# Humus_ethernet_dip_v4.net
KiCad netlist of a schematic drawn in EAGLE
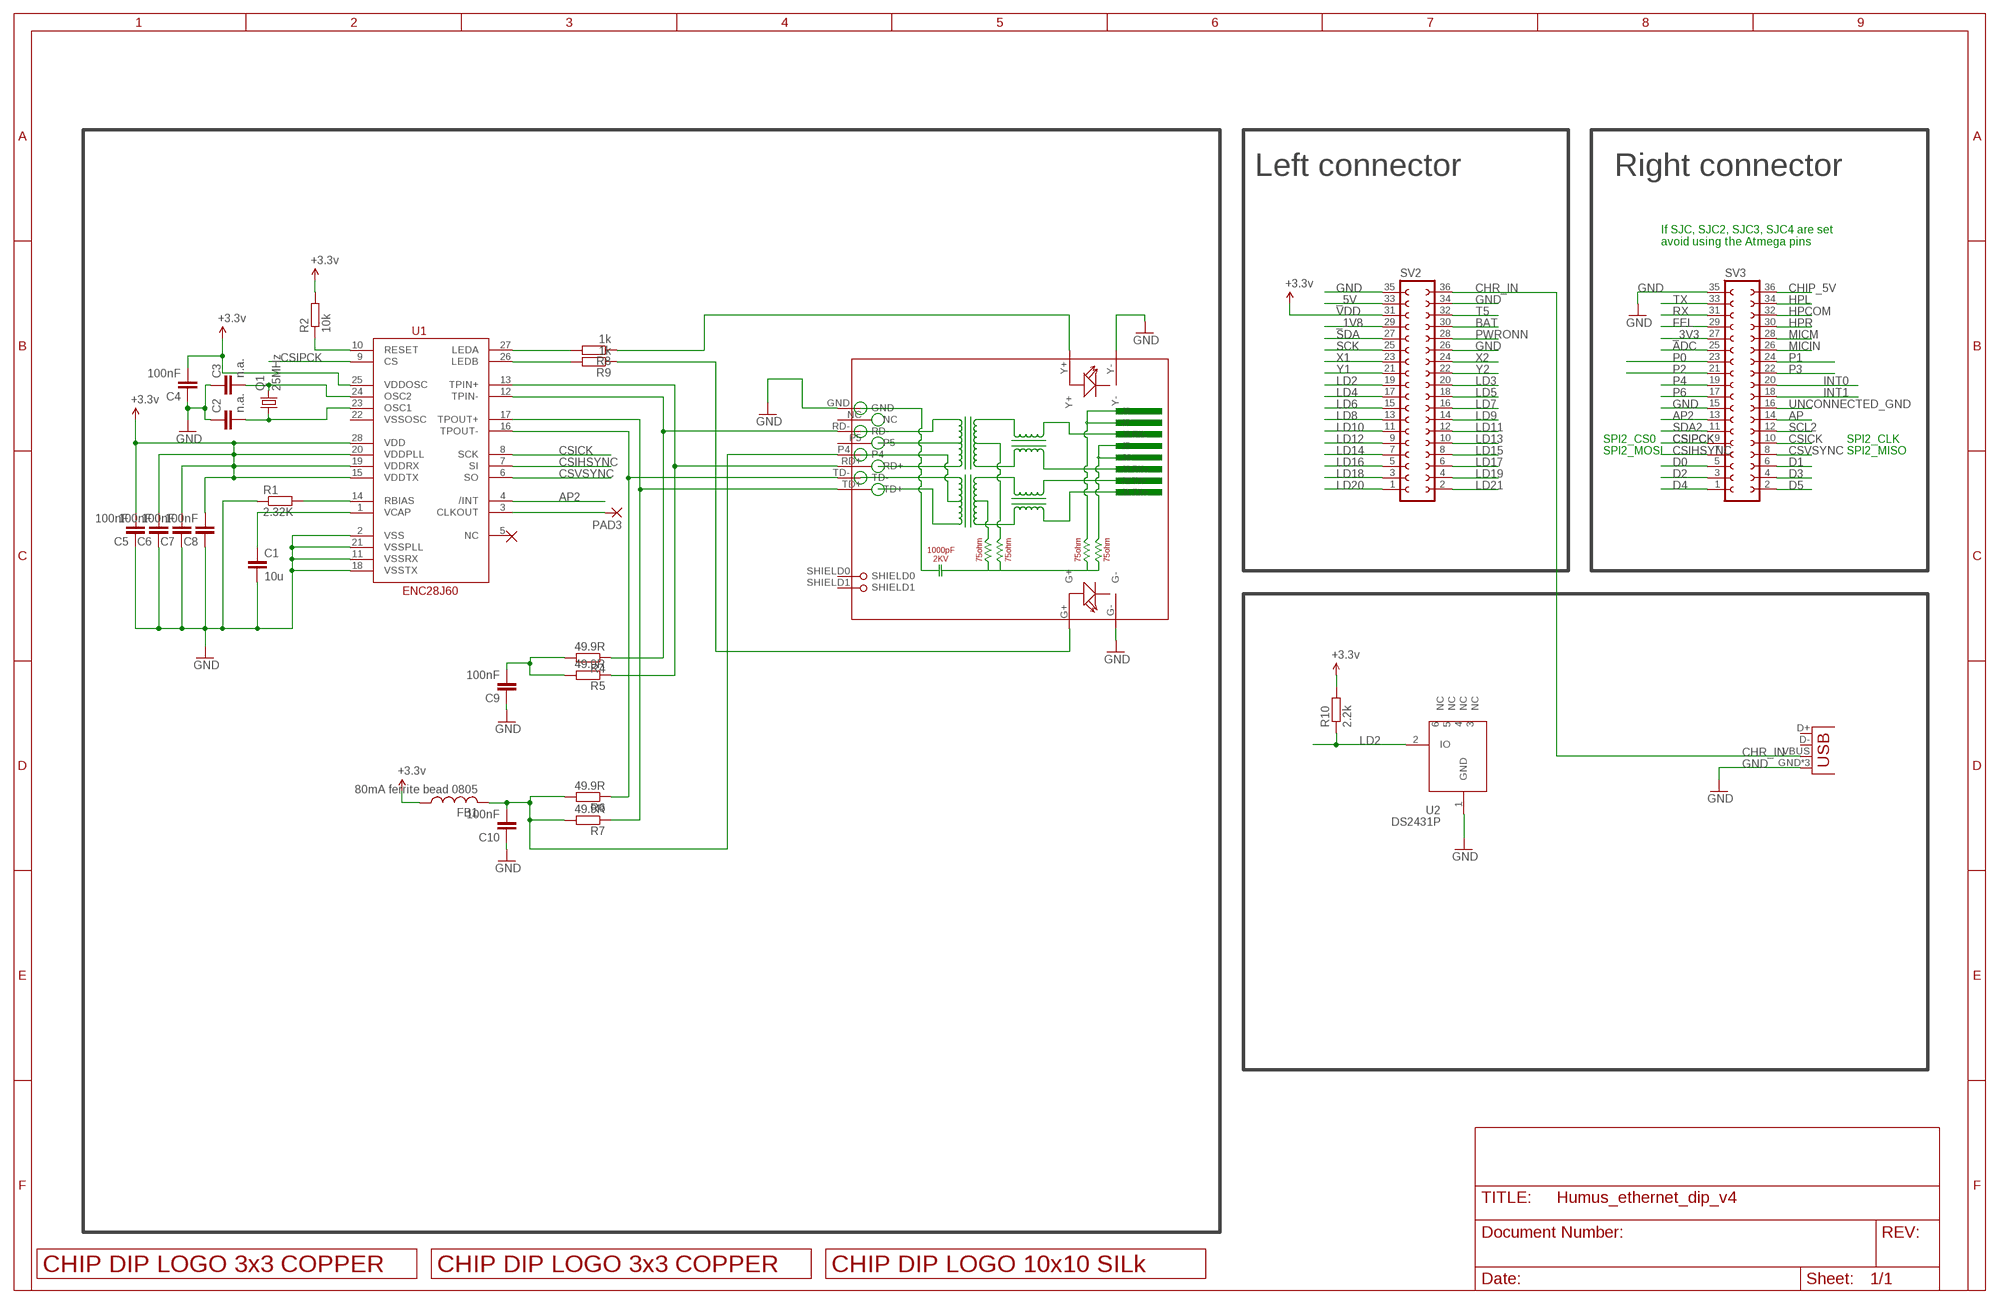
[diagram p0: schematic, sheet 1]

(export (version "E")
  (design (tool "Eeschema 10.0.6"))
  (components
    (comp (ref "C1")
      (value "10u")
      (footprint "eagle-import:C0805")
      (libsource (lib "eagle-import") (part "C-EUC0805"))
    )
    (comp (ref "C2")
      (value "n.a.")
      (footprint "eagle-import:C0805")
      (libsource (lib "eagle-import") (part "C-EUC0805"))
    )
    (comp (ref "C3")
      (value "n.a.")
      (footprint "eagle-import:C0805")
      (libsource (lib "eagle-import") (part "C-EUC0805"))
    )
    (comp (ref "C4")
      (value "100nF")
      (footprint "eagle-import:C0805")
      (libsource (lib "eagle-import") (part "C-EUC0805"))
    )
    (comp (ref "C5")
      (value "100nF")
      (footprint "eagle-import:C0805")
      (libsource (lib "eagle-import") (part "C-EUC0805"))
    )
    (comp (ref "C6")
      (value "100nF")
      (footprint "eagle-import:C0805")
      (libsource (lib "eagle-import") (part "C-EUC0805"))
    )
    (comp (ref "C7")
      (value "100nF")
      (footprint "eagle-import:C0805")
      (libsource (lib "eagle-import") (part "C-EUC0805"))
    )
    (comp (ref "C8")
      (value "100nF")
      (footprint "eagle-import:C0805")
      (libsource (lib "eagle-import") (part "C-EUC0805"))
    )
    (comp (ref "C9")
      (value "100nF")
      (footprint "eagle-import:C0805")
      (libsource (lib "eagle-import") (part "C-EUC0805"))
    )
    (comp (ref "C10")
      (value "100nF")
      (footprint "eagle-import:C0805")
      (libsource (lib "eagle-import") (part "C-EUC0805"))
    )
    (comp (ref "FB1")
      (value "80mA ferrite bead 0805")
      (footprint "eagle-import:0805")
      (libsource (lib "eagle-import") (part "FERRITE-BEADB"))
    )
    (comp (ref "PAD3")
      (value "WIREPADSMD1,27-254")
      (footprint "eagle-import:SMD1,27-2,54")
      (libsource (lib "eagle-import") (part "WIREPADSMD1,27-254"))
    )
    (comp (ref "Q1")
      (value "25MHz")
      (footprint "eagle-import:SM49")
      (libsource (lib "eagle-import") (part "CRYSTALSM49"))
    )
    (comp (ref "R1")
      (value "2.32K")
      (footprint "eagle-import:R0805")
      (libsource (lib "eagle-import") (part "R-EU_R0805"))
    )
    (comp (ref "R2")
      (value "10k")
      (footprint "eagle-import:R0805")
      (libsource (lib "eagle-import") (part "R-EU_R0805"))
    )
    (comp (ref "R4")
      (value "49.9R")
      (footprint "eagle-import:R0805")
      (libsource (lib "eagle-import") (part "R-EU_R0805"))
    )
    (comp (ref "R5")
      (value "49.9R")
      (footprint "eagle-import:R0805")
      (libsource (lib "eagle-import") (part "R-EU_R0805"))
    )
    (comp (ref "R6")
      (value "49.9R")
      (footprint "eagle-import:R0805")
      (libsource (lib "eagle-import") (part "R-EU_R0805"))
    )
    (comp (ref "R7")
      (value "49.9R")
      (footprint "eagle-import:R0805")
      (libsource (lib "eagle-import") (part "R-EU_R0805"))
    )
    (comp (ref "R8")
      (value "1k")
      (footprint "eagle-import:R0805")
      (libsource (lib "eagle-import") (part "R-EU_R0805"))
    )
    (comp (ref "R9")
      (value "1k")
      (footprint "eagle-import:R0805")
      (libsource (lib "eagle-import") (part "R-EU_R0805"))
    )
    (comp (ref "R10")
      (value "2.2k")
      (footprint "eagle-import:R0805")
      (libsource (lib "eagle-import") (part "R-EU_R0805"))
    )
    (comp (ref "RJ1")
      (value "HR911105A")
      (footprint "eagle-import:HR911105A")
      (libsource (lib "eagle-import") (part "HR911105A"))
    )
    (comp (ref "SV2")
      (value "FE18-2")
      (footprint "eagle-import:FE18-2")
      (libsource (lib "eagle-import") (part "FE18-2"))
    )
    (comp (ref "SV3")
      (value "FE18-2")
      (footprint "eagle-import:FE18-2")
      (libsource (lib "eagle-import") (part "FE18-2"))
    )
    (comp (ref "U$1")
      (value "LOGO_10X10_SILK")
      (footprint "eagle-import:LOGO2_10X10_SILK")
      (libsource (lib "eagle-import") (part "LOGO_10X10_SILK"))
    )
    (comp (ref "U$2")
      (value "LOGO_3X3_COPPER")
      (footprint "eagle-import:LOGO_3X3_COPPER")
      (libsource (lib "eagle-import") (part "LOGO_3X3_COPPER"))
    )
    (comp (ref "U$4")
      (value "LOGO_3X3_COPPER")
      (footprint "eagle-import:LOGO_3X3_COPPER")
      (libsource (lib "eagle-import") (part "LOGO_3X3_COPPER"))
    )
    (comp (ref "U1")
      (value "ENC28J60SS")
      (footprint "eagle-import:SSOP28DB")
      (libsource (lib "eagle-import") (part "ENC28J60"))
    )
    (comp (ref "U2")
      (value "DS2431P")
      (footprint "eagle-import:TSOC6")
      (fields (field (name "MFG") "DIGIKEY") (field (name "VENDOR_PART_NUMBER") "DS2431P+T&R"))
      (libsource (lib "eagle-import") (part "DS2431P"))
    )
    (comp (ref "USB")
      (value "USBUSB-MICROB-SMT-DIP")
      (footprint "eagle-import:USB-MICROB-SMT-DIP")
      (libsource (lib "eagle-import") (part "USBUSB-MICROB-SMT-DIP"))
    )
  )
  (nets
    (net (code "1") (name "+3.3v") (class "Default")
      (node (ref "C4") (pin "2") (pinfunction "2_2") (pintype "passive"))
      (node (ref "C5") (pin "2") (pinfunction "2_2") (pintype "passive"))
      (node (ref "C6") (pin "2") (pinfunction "2_2") (pintype "passive"))
      (node (ref "C7") (pin "2") (pinfunction "2_2") (pintype "passive"))
      (node (ref "C8") (pin "2") (pinfunction "2_2") (pintype "passive"))
      (node (ref "FB1") (pin "1") (pinfunction "1_1") (pintype "passive"))
      (node (ref "R10") (pin "2") (pinfunction "2_2") (pintype "passive"))
      (node (ref "R2") (pin "2") (pinfunction "2_2") (pintype "passive"))
      (node (ref "SV2") (pin "31") (pinfunction "31_31") (pintype "passive"))
      (node (ref "U1") (pin "15") (pinfunction "VDDTX_15") (pintype "bidirectional"))
      (node (ref "U1") (pin "19") (pinfunction "VDDRX_19") (pintype "bidirectional"))
      (node (ref "U1") (pin "20") (pinfunction "VDDPLL_20") (pintype "bidirectional"))
      (node (ref "U1") (pin "25") (pinfunction "VDDOSC_25") (pintype "bidirectional"))
      (node (ref "U1") (pin "28") (pinfunction "VDD_28") (pintype "bidirectional"))
    )
    (net (code "2") (name "/ADC") (class "Default")
      (node (ref "SV3") (pin "25") (pinfunction "25_25") (pintype "passive"))
    )
    (net (code "3") (name "/AP") (class "Default")
      (node (ref "SV3") (pin "14") (pinfunction "14_14") (pintype "passive"))
    )
    (net (code "4") (name "/AP2") (class "Default")
      (node (ref "SV3") (pin "13") (pinfunction "13_13") (pintype "passive"))
      (node (ref "U1") (pin "4") (pinfunction "/INT_4") (pintype "bidirectional"))
    )
    (net (code "5") (name "/BAT") (class "Default")
      (node (ref "SV2") (pin "30") (pinfunction "30_30") (pintype "passive"))
    )
    (net (code "6") (name "/CHIP_5V") (class "Default")
      (node (ref "SV3") (pin "36") (pinfunction "36_36") (pintype "passive"))
    )
    (net (code "7") (name "/CHR_IN") (class "Default")
      (node (ref "SV2") (pin "36") (pinfunction "36_36") (pintype "passive"))
      (node (ref "USB") (pin "VBUS") (pinfunction "VBUS_VBUS") (pintype "bidirectional"))
    )
    (net (code "8") (name "/CSICK") (class "Default")
      (node (ref "SV3") (pin "10") (pinfunction "10_10") (pintype "passive"))
      (node (ref "U1") (pin "8") (pinfunction "SCK_8") (pintype "bidirectional"))
    )
    (net (code "9") (name "/CSIHSYNC") (class "Default")
      (node (ref "SV3") (pin "7") (pinfunction "7_7") (pintype "passive"))
      (node (ref "U1") (pin "7") (pinfunction "SI_7") (pintype "bidirectional"))
    )
    (net (code "10") (name "/CSIPCK") (class "Default")
      (node (ref "SV3") (pin "9") (pinfunction "9_9") (pintype "passive"))
      (node (ref "U1") (pin "9") (pinfunction "CS_9") (pintype "bidirectional"))
    )
    (net (code "11") (name "/CSVSYNC") (class "Default")
      (node (ref "SV3") (pin "8") (pinfunction "8_8") (pintype "passive"))
      (node (ref "U1") (pin "6") (pinfunction "SO_6") (pintype "bidirectional"))
    )
    (net (code "12") (name "/D0") (class "Default")
      (node (ref "SV3") (pin "5") (pinfunction "5_5") (pintype "passive"))
    )
    (net (code "13") (name "/D1") (class "Default")
      (node (ref "SV3") (pin "6") (pinfunction "6_6") (pintype "passive"))
    )
    (net (code "14") (name "/D2") (class "Default")
      (node (ref "SV3") (pin "3") (pinfunction "3_3") (pintype "passive"))
    )
    (net (code "15") (name "/D3") (class "Default")
      (node (ref "SV3") (pin "4") (pinfunction "4_4") (pintype "passive"))
    )
    (net (code "16") (name "/D4") (class "Default")
      (node (ref "SV3") (pin "1") (pinfunction "1_1") (pintype "passive"))
    )
    (net (code "17") (name "/D5") (class "Default")
      (node (ref "SV3") (pin "2") (pinfunction "2_2") (pintype "passive"))
    )
    (net (code "18") (name "/FEL") (class "Default")
      (node (ref "SV3") (pin "29") (pinfunction "29_29") (pintype "passive"))
    )
    (net (code "19") (name "/HPCOM") (class "Default")
      (node (ref "SV3") (pin "32") (pinfunction "32_32") (pintype "passive"))
    )
    (net (code "20") (name "/HPL") (class "Default")
      (node (ref "SV3") (pin "34") (pinfunction "34_34") (pintype "passive"))
    )
    (net (code "21") (name "/HPR") (class "Default")
      (node (ref "SV3") (pin "30") (pinfunction "30_30") (pintype "passive"))
    )
    (net (code "22") (name "/INT0") (class "Default")
      (node (ref "SV3") (pin "20") (pinfunction "20_20") (pintype "passive"))
    )
    (net (code "23") (name "/INT1") (class "Default")
      (node (ref "SV3") (pin "18") (pinfunction "18_18") (pintype "passive"))
    )
    (net (code "24") (name "/LD2") (class "Default")
      (node (ref "R10") (pin "1") (pinfunction "1_1") (pintype "passive"))
      (node (ref "SV2") (pin "19") (pinfunction "19_19") (pintype "passive"))
      (node (ref "U2") (pin "2") (pinfunction "IO_2") (pintype "bidirectional"))
    )
    (net (code "25") (name "/LD3") (class "Default")
      (node (ref "SV2") (pin "20") (pinfunction "20_20") (pintype "passive"))
    )
    (net (code "26") (name "/LD4") (class "Default")
      (node (ref "SV2") (pin "17") (pinfunction "17_17") (pintype "passive"))
    )
    (net (code "27") (name "/LD5") (class "Default")
      (node (ref "SV2") (pin "18") (pinfunction "18_18") (pintype "passive"))
    )
    (net (code "28") (name "/LD6") (class "Default")
      (node (ref "SV2") (pin "15") (pinfunction "15_15") (pintype "passive"))
    )
    (net (code "29") (name "/LD7") (class "Default")
      (node (ref "SV2") (pin "16") (pinfunction "16_16") (pintype "passive"))
    )
    (net (code "30") (name "/LD8") (class "Default")
      (node (ref "SV2") (pin "13") (pinfunction "13_13") (pintype "passive"))
    )
    (net (code "31") (name "/LD9") (class "Default")
      (node (ref "SV2") (pin "14") (pinfunction "14_14") (pintype "passive"))
    )
    (net (code "32") (name "/LD10") (class "Default")
      (node (ref "SV2") (pin "11") (pinfunction "11_11") (pintype "passive"))
    )
    (net (code "33") (name "/LD11") (class "Default")
      (node (ref "SV2") (pin "12") (pinfunction "12_12") (pintype "passive"))
    )
    (net (code "34") (name "/LD12") (class "Default")
      (node (ref "SV2") (pin "9") (pinfunction "9_9") (pintype "passive"))
    )
    (net (code "35") (name "/LD13") (class "Default")
      (node (ref "SV2") (pin "10") (pinfunction "10_10") (pintype "passive"))
    )
    (net (code "36") (name "/LD14") (class "Default")
      (node (ref "SV2") (pin "7") (pinfunction "7_7") (pintype "passive"))
    )
    (net (code "37") (name "/LD15") (class "Default")
      (node (ref "SV2") (pin "8") (pinfunction "8_8") (pintype "passive"))
    )
    (net (code "38") (name "/LD16") (class "Default")
      (node (ref "SV2") (pin "5") (pinfunction "5_5") (pintype "passive"))
    )
    (net (code "39") (name "/LD17") (class "Default")
      (node (ref "SV2") (pin "6") (pinfunction "6_6") (pintype "passive"))
    )
    (net (code "40") (name "/LD18") (class "Default")
      (node (ref "SV2") (pin "3") (pinfunction "3_3") (pintype "passive"))
    )
    (net (code "41") (name "/LD19") (class "Default")
      (node (ref "SV2") (pin "4") (pinfunction "4_4") (pintype "passive"))
    )
    (net (code "42") (name "/LD20") (class "Default")
      (node (ref "SV2") (pin "1") (pinfunction "1_1") (pintype "passive"))
    )
    (net (code "43") (name "/LD21") (class "Default")
      (node (ref "SV2") (pin "2") (pinfunction "2_2") (pintype "passive"))
    )
    (net (code "44") (name "/MICIN") (class "Default")
      (node (ref "SV3") (pin "26") (pinfunction "26_26") (pintype "passive"))
    )
    (net (code "45") (name "/MICM") (class "Default")
      (node (ref "SV3") (pin "28") (pinfunction "28_28") (pintype "passive"))
    )
    (net (code "46") (name "/P0") (class "Default")
      (node (ref "SV3") (pin "23") (pinfunction "23_23") (pintype "passive"))
    )
    (net (code "47") (name "/P1") (class "Default")
      (node (ref "SV3") (pin "24") (pinfunction "24_24") (pintype "passive"))
    )
    (net (code "48") (name "/P2") (class "Default")
      (node (ref "SV3") (pin "21") (pinfunction "21_21") (pintype "passive"))
    )
    (net (code "49") (name "/P3") (class "Default")
      (node (ref "SV3") (pin "22") (pinfunction "22_22") (pintype "passive"))
    )
    (net (code "50") (name "/P4") (class "Default")
      (node (ref "SV3") (pin "19") (pinfunction "19_19") (pintype "passive"))
    )
    (net (code "51") (name "/P6") (class "Default")
      (node (ref "SV3") (pin "17") (pinfunction "17_17") (pintype "passive"))
    )
    (net (code "52") (name "/PWRONN") (class "Default")
      (node (ref "SV2") (pin "28") (pinfunction "28_28") (pintype "passive"))
    )
    (net (code "53") (name "/RX") (class "Default")
      (node (ref "SV3") (pin "31") (pinfunction "31_31") (pintype "passive"))
    )
    (net (code "54") (name "/SCK") (class "Default")
      (node (ref "SV2") (pin "25") (pinfunction "25_25") (pintype "passive"))
    )
    (net (code "55") (name "/SCL2") (class "Default")
      (node (ref "SV3") (pin "12") (pinfunction "12_12") (pintype "passive"))
    )
    (net (code "56") (name "/SDA") (class "Default")
      (node (ref "SV2") (pin "27") (pinfunction "27_27") (pintype "passive"))
    )
    (net (code "57") (name "/SDA2") (class "Default")
      (node (ref "SV3") (pin "11") (pinfunction "11_11") (pintype "passive"))
    )
    (net (code "58") (name "/T5") (class "Default")
      (node (ref "SV2") (pin "32") (pinfunction "32_32") (pintype "passive"))
    )
    (net (code "59") (name "/TX") (class "Default")
      (node (ref "SV3") (pin "33") (pinfunction "33_33") (pintype "passive"))
    )
    (net (code "60") (name "/UNCONNECTED_GND") (class "Default")
      (node (ref "SV3") (pin "16") (pinfunction "16_16") (pintype "passive"))
    )
    (net (code "61") (name "/X1") (class "Default")
      (node (ref "SV2") (pin "23") (pinfunction "23_23") (pintype "passive"))
    )
    (net (code "62") (name "/X2") (class "Default")
      (node (ref "SV2") (pin "24") (pinfunction "24_24") (pintype "passive"))
    )
    (net (code "63") (name "/Y1") (class "Default")
      (node (ref "SV2") (pin "21") (pinfunction "21_21") (pintype "passive"))
    )
    (net (code "64") (name "/Y2") (class "Default")
      (node (ref "SV2") (pin "22") (pinfunction "22_22") (pintype "passive"))
    )
    (net (code "65") (name "/_1V8") (class "Default")
      (node (ref "SV2") (pin "29") (pinfunction "29_29") (pintype "passive"))
    )
    (net (code "66") (name "/_3V3") (class "Default")
      (node (ref "SV3") (pin "27") (pinfunction "27_27") (pintype "passive"))
    )
    (net (code "67") (name "/_5V") (class "Default")
      (node (ref "SV2") (pin "33") (pinfunction "33_33") (pintype "passive"))
    )
    (net (code "68") (name "GND") (class "Default")
      (node (ref "C1") (pin "2") (pinfunction "2_2") (pintype "passive"))
      (node (ref "C10") (pin "1") (pinfunction "1_1") (pintype "passive"))
      (node (ref "C2") (pin "1") (pinfunction "1_1") (pintype "passive"))
      (node (ref "C3") (pin "1") (pinfunction "1_1") (pintype "passive"))
      (node (ref "C4") (pin "1") (pinfunction "1_1") (pintype "passive"))
      (node (ref "C5") (pin "1") (pinfunction "1_1") (pintype "passive"))
      (node (ref "C6") (pin "1") (pinfunction "1_1") (pintype "passive"))
      (node (ref "C7") (pin "1") (pinfunction "1_1") (pintype "passive"))
      (node (ref "C8") (pin "1") (pinfunction "1_1") (pintype "passive"))
      (node (ref "C9") (pin "1") (pinfunction "1_1") (pintype "passive"))
      (node (ref "R1") (pin "1") (pinfunction "1_1") (pintype "passive"))
      (node (ref "RJ1") (pin "G-") (pinfunction "G-_G-") (pintype "bidirectional"))
      (node (ref "RJ1") (pin "GND") (pinfunction "GND_GND") (pintype "bidirectional"))
      (node (ref "RJ1") (pin "Y-") (pinfunction "Y-_Y-") (pintype "bidirectional"))
      (node (ref "SV2") (pin "26") (pinfunction "26_26") (pintype "passive"))
      (node (ref "SV2") (pin "34") (pinfunction "34_34") (pintype "passive"))
      (node (ref "SV2") (pin "35") (pinfunction "35_35") (pintype "passive"))
      (node (ref "SV3") (pin "15") (pinfunction "15_15") (pintype "passive"))
      (node (ref "SV3") (pin "35") (pinfunction "35_35") (pintype "passive"))
      (node (ref "U1") (pin "11") (pinfunction "VSSRX_11") (pintype "bidirectional"))
      (node (ref "U1") (pin "18") (pinfunction "VSSTX_18") (pintype "bidirectional"))
      (node (ref "U1") (pin "2") (pinfunction "VSS_2") (pintype "bidirectional"))
      (node (ref "U1") (pin "21") (pinfunction "VSSPLL_21") (pintype "bidirectional"))
      (node (ref "U2") (pin "1") (pinfunction "GND_1") (pintype "bidirectional"))
      (node (ref "USB") (pin "GND") (pinfunction "GND_GND") (pintype "bidirectional"))
      (node (ref "USB") (pin "MT1") (pinfunction "GND_MT1") (pintype "bidirectional"))
      (node (ref "USB") (pin "MT2") (pinfunction "GND_MT2") (pintype "bidirectional"))
    )
    (net (code "69") (name "Net-(C9-Pad2)") (class "Default")
      (node (ref "C9") (pin "2") (pinfunction "2_2") (pintype "passive"))
      (node (ref "R4") (pin "2") (pinfunction "2_2") (pintype "passive"))
      (node (ref "R5") (pin "2") (pinfunction "2_2") (pintype "passive"))
    )
    (net (code "70") (name "Net-(C10-Pad2)") (class "Default")
      (node (ref "C10") (pin "2") (pinfunction "2_2") (pintype "passive"))
      (node (ref "FB1") (pin "2") (pinfunction "2_2") (pintype "passive"))
      (node (ref "R6") (pin "2") (pinfunction "2_2") (pintype "passive"))
      (node (ref "R7") (pin "2") (pinfunction "2_2") (pintype "passive"))
      (node (ref "RJ1") (pin "P4") (pinfunction "P4_P4") (pintype "bidirectional"))
    )
    (net (code "71") (name "Net-(PAD3-P)") (class "Default")
      (node (ref "PAD3") (pin "1") (pinfunction "P_1") (pintype "passive"))
      (node (ref "U1") (pin "3") (pinfunction "CLKOUT_3") (pintype "bidirectional"))
    )
    (net (code "72") (name "Net-(R8-Pad1)") (class "Default")
      (node (ref "R8") (pin "1") (pinfunction "1_1") (pintype "passive"))
      (node (ref "RJ1") (pin "Y+") (pinfunction "Y+_Y+") (pintype "bidirectional"))
    )
    (net (code "73") (name "Net-(R9-Pad1)") (class "Default")
      (node (ref "R9") (pin "1") (pinfunction "1_1") (pintype "passive"))
      (node (ref "RJ1") (pin "G+") (pinfunction "G+_G+") (pintype "bidirectional"))
    )
    (net (code "74") (name "Net-(U1-LEDA)") (class "Default")
      (node (ref "R8") (pin "2") (pinfunction "2_2") (pintype "passive"))
      (node (ref "U1") (pin "27") (pinfunction "LEDA_27") (pintype "bidirectional"))
    )
    (net (code "75") (name "Net-(U1-LEDB)") (class "Default")
      (node (ref "R9") (pin "2") (pinfunction "2_2") (pintype "passive"))
      (node (ref "U1") (pin "26") (pinfunction "LEDB_26") (pintype "bidirectional"))
    )
    (net (code "76") (name "Net-(U1-OSC1)") (class "Default")
      (node (ref "C2") (pin "2") (pinfunction "2_2") (pintype "passive"))
      (node (ref "Q1") (pin "1") (pinfunction "1_1") (pintype "passive"))
      (node (ref "U1") (pin "23") (pinfunction "OSC1_23") (pintype "bidirectional"))
    )
    (net (code "77") (name "Net-(U1-OSC2)") (class "Default")
      (node (ref "C3") (pin "2") (pinfunction "2_2") (pintype "passive"))
      (node (ref "Q1") (pin "2") (pinfunction "2_2") (pintype "passive"))
      (node (ref "U1") (pin "24") (pinfunction "OSC2_24") (pintype "bidirectional"))
    )
    (net (code "78") (name "Net-(U1-RBIAS)") (class "Default")
      (node (ref "R1") (pin "2") (pinfunction "2_2") (pintype "passive"))
      (node (ref "U1") (pin "14") (pinfunction "RBIAS_14") (pintype "bidirectional"))
    )
    (net (code "79") (name "Net-(U1-RESET)") (class "Default")
      (node (ref "R2") (pin "1") (pinfunction "1_1") (pintype "passive"))
      (node (ref "U1") (pin "10") (pinfunction "RESET_10") (pintype "bidirectional"))
    )
    (net (code "80") (name "Net-(U1-TPIN+)") (class "Default")
      (node (ref "R5") (pin "1") (pinfunction "1_1") (pintype "passive"))
      (node (ref "RJ1") (pin "RD+") (pinfunction "RD+_RD+") (pintype "bidirectional"))
      (node (ref "U1") (pin "13") (pinfunction "TPIN+_13") (pintype "bidirectional"))
    )
    (net (code "81") (name "Net-(U1-TPIN-)") (class "Default")
      (node (ref "R4") (pin "1") (pinfunction "1_1") (pintype "passive"))
      (node (ref "RJ1") (pin "RD-") (pinfunction "RD-_RD-") (pintype "bidirectional"))
      (node (ref "U1") (pin "12") (pinfunction "TPIN-_12") (pintype "bidirectional"))
    )
    (net (code "82") (name "Net-(U1-TPOUT+)") (class "Default")
      (node (ref "R7") (pin "1") (pinfunction "1_1") (pintype "passive"))
      (node (ref "RJ1") (pin "TD+") (pinfunction "TD+_TD+") (pintype "bidirectional"))
      (node (ref "U1") (pin "17") (pinfunction "TPOUT+_17") (pintype "bidirectional"))
    )
    (net (code "83") (name "Net-(U1-TPOUT-)") (class "Default")
      (node (ref "R6") (pin "1") (pinfunction "1_1") (pintype "passive"))
      (node (ref "RJ1") (pin "TD-") (pinfunction "TD-_TD-") (pintype "bidirectional"))
      (node (ref "U1") (pin "16") (pinfunction "TPOUT-_16") (pintype "bidirectional"))
    )
    (net (code "84") (name "Net-(U1-VCAP)") (class "Default")
      (node (ref "C1") (pin "1") (pinfunction "1_1") (pintype "passive"))
      (node (ref "U1") (pin "1") (pinfunction "VCAP_1") (pintype "bidirectional"))
    )
    (net (code "85") (name "unconnected-(RJ1-PadNC)") (class "Default")
      (node (ref "RJ1") (pin "NC") (pinfunction "NC_NC") (pintype "bidirectional"))
    )
    (net (code "86") (name "unconnected-(RJ1-PadP5)") (class "Default")
      (node (ref "RJ1") (pin "P5") (pinfunction "P5_P5") (pintype "bidirectional"))
    )
    (net (code "87") (name "unconnected-(RJ1-PadSHIELD0)") (class "Default")
      (node (ref "RJ1") (pin "SHIELD0") (pinfunction "SHIELD0_SHIELD0") (pintype "bidirectional"))
    )
    (net (code "88") (name "unconnected-(RJ1-PadSHIELD1)") (class "Default")
      (node (ref "RJ1") (pin "SHIELD1") (pinfunction "SHIELD1_SHIELD1") (pintype "bidirectional"))
    )
    (net (code "89") (name "unconnected-(U1-NC-Pad5)") (class "Default")
      (node (ref "U1") (pin "5") (pinfunction "NC_5") (pintype "bidirectional"))
    )
    (net (code "90") (name "unconnected-(U1-VSSOSC-Pad22)") (class "Default")
      (node (ref "U1") (pin "22") (pinfunction "VSSOSC_22") (pintype "bidirectional"))
    )
    (net (code "91") (name "unconnected-(U2-NC-Pad3)") (class "Default")
      (node (ref "U2") (pin "3") (pinfunction "NC_3") (pintype "bidirectional"))
    )
    (net (code "92") (name "unconnected-(U2-NC-Pad4)") (class "Default")
      (node (ref "U2") (pin "4") (pinfunction "NC_4") (pintype "bidirectional"))
    )
    (net (code "93") (name "unconnected-(U2-NC-Pad5)") (class "Default")
      (node (ref "U2") (pin "5") (pinfunction "NC_5") (pintype "bidirectional"))
    )
    (net (code "94") (name "unconnected-(U2-NC-Pad6)") (class "Default")
      (node (ref "U2") (pin "6") (pinfunction "NC_6") (pintype "bidirectional"))
    )
    (net (code "95") (name "unconnected-(USB-PadD+)") (class "Default")
      (node (ref "USB") (pin "D+") (pinfunction "D+_D+") (pintype "bidirectional"))
    )
    (net (code "96") (name "unconnected-(USB-PadD-)") (class "Default")
      (node (ref "USB") (pin "D-") (pinfunction "D-_D-") (pintype "bidirectional"))
    )
  )
)
